# ERC_Sch_1.net
KiCad netlist of a schematic drawn in EAGLE
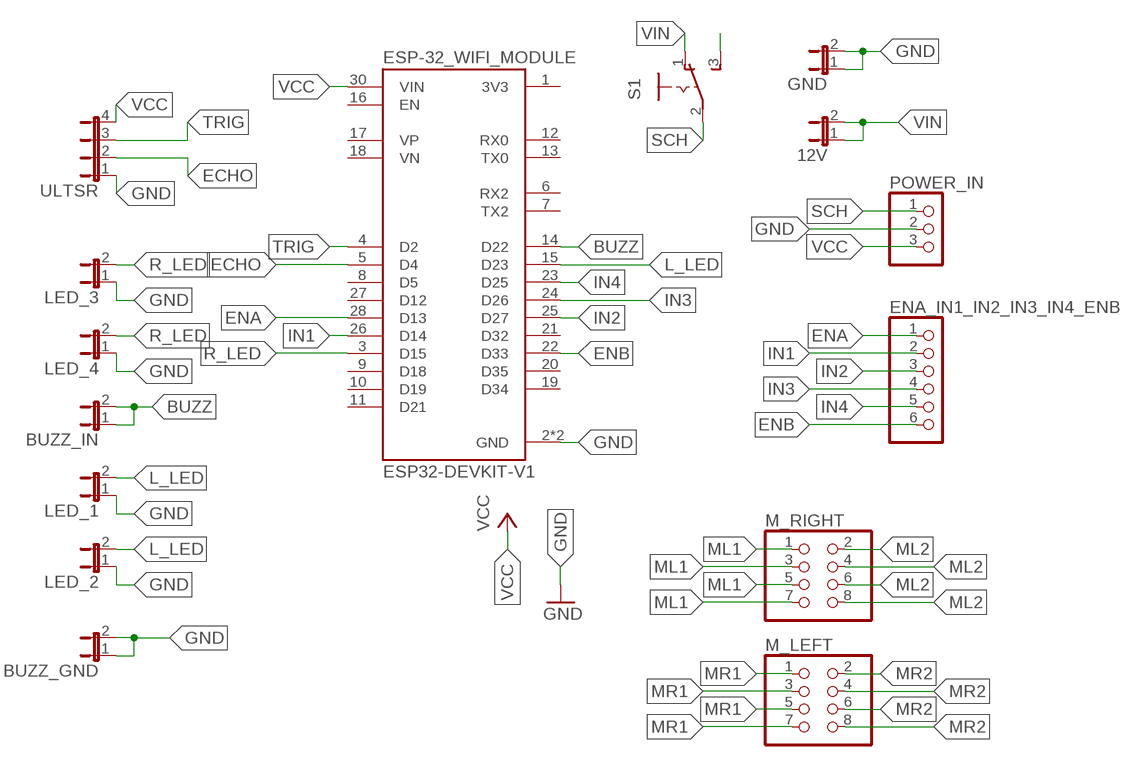
[diagram p0: schematic, sheet 1]

(export (version "E")
  (design (tool "Eeschema 10.0.6"))
  (components
    (comp (ref "12V")
      (value "JP1E")
      (footprint "eagle-import:JP1")
      (libsource (lib "eagle-import") (part "JP1E"))
    )
    (comp (ref "BUZZ_GND")
      (value "JP1E")
      (footprint "eagle-import:JP1")
      (libsource (lib "eagle-import") (part "JP1E"))
    )
    (comp (ref "BUZZ_IN")
      (value "JP1E")
      (footprint "eagle-import:JP1")
      (libsource (lib "eagle-import") (part "JP1E"))
    )
    (comp (ref "ENA_IN1_IN2_IN3_IN4_ENB")
      (value "PINHD-1X6")
      (footprint "eagle-import:1X06")
      (libsource (lib "eagle-import") (part "PINHD-1X6"))
    )
    (comp (ref "ESP-32_WIFI_MODULE")
      (value "ESP32-DEVKIT-V1")
      (footprint "eagle-import:MODULE_ESP32_DEVKIT_V1")
      (fields (field (name "MF") "Do it"))
      (libsource (lib "eagle-import") (part "ESP32-DEVKIT-V1"))
    )
    (comp (ref "GND")
      (value "JP1E")
      (footprint "eagle-import:JP1")
      (libsource (lib "eagle-import") (part "JP1E"))
    )
    (comp (ref "LED_1")
      (value "JP1E")
      (footprint "eagle-import:JP1")
      (libsource (lib "eagle-import") (part "JP1E"))
    )
    (comp (ref "LED_2")
      (value "JP1E")
      (footprint "eagle-import:JP1")
      (libsource (lib "eagle-import") (part "JP1E"))
    )
    (comp (ref "LED_3")
      (value "JP1E")
      (footprint "eagle-import:JP1")
      (libsource (lib "eagle-import") (part "JP1E"))
    )
    (comp (ref "LED_4")
      (value "JP1E")
      (footprint "eagle-import:JP1")
      (libsource (lib "eagle-import") (part "JP1E"))
    )
    (comp (ref "M_LEFT")
      (value "PINHD-2X4")
      (footprint "eagle-import:2X04")
      (libsource (lib "eagle-import") (part "PINHD-2X4"))
    )
    (comp (ref "M_RIGHT")
      (value "PINHD-2X4")
      (footprint "eagle-import:2X04")
      (libsource (lib "eagle-import") (part "PINHD-2X4"))
    )
    (comp (ref "POWER_IN")
      (value "PINHD-1X3")
      (footprint "eagle-import:1X03")
      (libsource (lib "eagle-import") (part "PINHD-1X3"))
    )
    (comp (ref "S1")
      (value "255SB")
      (footprint "eagle-import:255SB")
      (libsource (lib "eagle-import") (part "255SB"))
    )
    (comp (ref "ULTSR")
      (value "JP4E")
      (footprint "eagle-import:JP4")
      (libsource (lib "eagle-import") (part "JP4E"))
    )
  )
  (nets
    (net (code "1") (name "BUZZ") (class "Default")
      (node (ref "BUZZ_IN") (pin "1") (pinfunction "1_1") (pintype "passive"))
      (node (ref "BUZZ_IN") (pin "2") (pinfunction "2_2") (pintype "passive"))
      (node (ref "ESP-32_WIFI_MODULE") (pin "14") (pinfunction "D22_14") (pintype "bidirectional"))
    )
    (net (code "2") (name "ECHO") (class "Default")
      (node (ref "ESP-32_WIFI_MODULE") (pin "5") (pinfunction "D4_5") (pintype "bidirectional"))
      (node (ref "ULTSR") (pin "2") (pinfunction "2_2") (pintype "passive"))
    )
    (net (code "3") (name "ENA") (class "Default")
      (node (ref "ENA_IN1_IN2_IN3_IN4_ENB") (pin "1") (pinfunction "1_1") (pintype "passive"))
      (node (ref "ESP-32_WIFI_MODULE") (pin "28") (pinfunction "D13_28") (pintype "bidirectional"))
    )
    (net (code "4") (name "ENB") (class "Default")
      (node (ref "ENA_IN1_IN2_IN3_IN4_ENB") (pin "6") (pinfunction "6_6") (pintype "passive"))
      (node (ref "ESP-32_WIFI_MODULE") (pin "22") (pinfunction "D33_22") (pintype "bidirectional"))
    )
    (net (code "5") (name "GND") (class "Default")
      (node (ref "BUZZ_GND") (pin "1") (pinfunction "1_1") (pintype "passive"))
      (node (ref "BUZZ_GND") (pin "2") (pinfunction "2_2") (pintype "passive"))
      (node (ref "ESP-32_WIFI_MODULE") (pin "2") (pinfunction "GND_2") (pintype "power_in"))
      (node (ref "ESP-32_WIFI_MODULE") (pin "29") (pinfunction "GND_29") (pintype "power_in"))
      (node (ref "GND") (pin "1") (pinfunction "1_1") (pintype "passive"))
      (node (ref "GND") (pin "2") (pinfunction "2_2") (pintype "passive"))
      (node (ref "LED_1") (pin "1") (pinfunction "1_1") (pintype "passive"))
      (node (ref "LED_2") (pin "1") (pinfunction "1_1") (pintype "passive"))
      (node (ref "LED_3") (pin "1") (pinfunction "1_1") (pintype "passive"))
      (node (ref "LED_4") (pin "1") (pinfunction "1_1") (pintype "passive"))
      (node (ref "POWER_IN") (pin "2") (pinfunction "2_2") (pintype "passive"))
      (node (ref "ULTSR") (pin "1") (pinfunction "1_1") (pintype "passive"))
    )
    (net (code "6") (name "IN1") (class "Default")
      (node (ref "ENA_IN1_IN2_IN3_IN4_ENB") (pin "2") (pinfunction "2_2") (pintype "passive"))
      (node (ref "ESP-32_WIFI_MODULE") (pin "26") (pinfunction "D14_26") (pintype "bidirectional"))
    )
    (net (code "7") (name "IN2") (class "Default")
      (node (ref "ENA_IN1_IN2_IN3_IN4_ENB") (pin "3") (pinfunction "3_3") (pintype "passive"))
      (node (ref "ESP-32_WIFI_MODULE") (pin "25") (pinfunction "D27_25") (pintype "bidirectional"))
    )
    (net (code "8") (name "IN3") (class "Default")
      (node (ref "ENA_IN1_IN2_IN3_IN4_ENB") (pin "4") (pinfunction "4_4") (pintype "passive"))
      (node (ref "ESP-32_WIFI_MODULE") (pin "24") (pinfunction "D26_24") (pintype "bidirectional"))
    )
    (net (code "9") (name "IN4") (class "Default")
      (node (ref "ENA_IN1_IN2_IN3_IN4_ENB") (pin "5") (pinfunction "5_5") (pintype "passive"))
      (node (ref "ESP-32_WIFI_MODULE") (pin "23") (pinfunction "D25_23") (pintype "bidirectional"))
    )
    (net (code "10") (name "L_LED") (class "Default")
      (node (ref "ESP-32_WIFI_MODULE") (pin "15") (pinfunction "D23_15") (pintype "bidirectional"))
      (node (ref "LED_1") (pin "2") (pinfunction "2_2") (pintype "passive"))
      (node (ref "LED_2") (pin "2") (pinfunction "2_2") (pintype "passive"))
    )
    (net (code "11") (name "ML1") (class "Default")
      (node (ref "M_RIGHT") (pin "1") (pinfunction "1_1") (pintype "passive"))
      (node (ref "M_RIGHT") (pin "3") (pinfunction "3_3") (pintype "passive"))
      (node (ref "M_RIGHT") (pin "5") (pinfunction "5_5") (pintype "passive"))
      (node (ref "M_RIGHT") (pin "7") (pinfunction "7_7") (pintype "passive"))
    )
    (net (code "12") (name "ML2") (class "Default")
      (node (ref "M_RIGHT") (pin "2") (pinfunction "2_2") (pintype "passive"))
      (node (ref "M_RIGHT") (pin "4") (pinfunction "4_4") (pintype "passive"))
      (node (ref "M_RIGHT") (pin "6") (pinfunction "6_6") (pintype "passive"))
      (node (ref "M_RIGHT") (pin "8") (pinfunction "8_8") (pintype "passive"))
    )
    (net (code "13") (name "MR1") (class "Default")
      (node (ref "M_LEFT") (pin "1") (pinfunction "1_1") (pintype "passive"))
      (node (ref "M_LEFT") (pin "3") (pinfunction "3_3") (pintype "passive"))
      (node (ref "M_LEFT") (pin "5") (pinfunction "5_5") (pintype "passive"))
      (node (ref "M_LEFT") (pin "7") (pinfunction "7_7") (pintype "passive"))
    )
    (net (code "14") (name "MR2") (class "Default")
      (node (ref "M_LEFT") (pin "2") (pinfunction "2_2") (pintype "passive"))
      (node (ref "M_LEFT") (pin "4") (pinfunction "4_4") (pintype "passive"))
      (node (ref "M_LEFT") (pin "6") (pinfunction "6_6") (pintype "passive"))
      (node (ref "M_LEFT") (pin "8") (pinfunction "8_8") (pintype "passive"))
    )
    (net (code "15") (name "R_LED") (class "Default")
      (node (ref "ESP-32_WIFI_MODULE") (pin "3") (pinfunction "D15_3") (pintype "bidirectional"))
      (node (ref "LED_3") (pin "2") (pinfunction "2_2") (pintype "passive"))
      (node (ref "LED_4") (pin "2") (pinfunction "2_2") (pintype "passive"))
    )
    (net (code "16") (name "SCH") (class "Default")
      (node (ref "POWER_IN") (pin "1") (pinfunction "1_1") (pintype "passive"))
      (node (ref "S1") (pin "2") (pinfunction "P_2") (pintype "passive"))
    )
    (net (code "17") (name "TRIG") (class "Default")
      (node (ref "ESP-32_WIFI_MODULE") (pin "4") (pinfunction "D2_4") (pintype "bidirectional"))
      (node (ref "ULTSR") (pin "3") (pinfunction "3_3") (pintype "passive"))
    )
    (net (code "18") (name "VCC") (class "Default")
      (node (ref "ESP-32_WIFI_MODULE") (pin "30") (pinfunction "VIN_30") (pintype "input"))
      (node (ref "POWER_IN") (pin "3") (pinfunction "3_3") (pintype "passive"))
      (node (ref "ULTSR") (pin "4") (pinfunction "4_4") (pintype "passive"))
    )
    (net (code "19") (name "VIN") (class "Default")
      (node (ref "12V") (pin "1") (pinfunction "1_1") (pintype "passive"))
      (node (ref "12V") (pin "2") (pinfunction "2_2") (pintype "passive"))
      (node (ref "S1") (pin "1") (pinfunction "O_1") (pintype "passive"))
    )
    (net (code "20") (name "unconnected-(ESP-32_WIFI_MODULE-3V3-Pad1)") (class "Default")
      (node (ref "ESP-32_WIFI_MODULE") (pin "1") (pinfunction "3V3_1") (pintype "output"))
    )
    (net (code "21") (name "unconnected-(ESP-32_WIFI_MODULE-D5-Pad8)") (class "Default")
      (node (ref "ESP-32_WIFI_MODULE") (pin "8") (pinfunction "D5_8") (pintype "bidirectional"))
    )
    (net (code "22") (name "unconnected-(ESP-32_WIFI_MODULE-D12-Pad27)") (class "Default")
      (node (ref "ESP-32_WIFI_MODULE") (pin "27") (pinfunction "D12_27") (pintype "bidirectional"))
    )
    (net (code "23") (name "unconnected-(ESP-32_WIFI_MODULE-D18-Pad9)") (class "Default")
      (node (ref "ESP-32_WIFI_MODULE") (pin "9") (pinfunction "D18_9") (pintype "bidirectional"))
    )
    (net (code "24") (name "unconnected-(ESP-32_WIFI_MODULE-D19-Pad10)") (class "Default")
      (node (ref "ESP-32_WIFI_MODULE") (pin "10") (pinfunction "D19_10") (pintype "bidirectional"))
    )
    (net (code "25") (name "unconnected-(ESP-32_WIFI_MODULE-D21-Pad11)") (class "Default")
      (node (ref "ESP-32_WIFI_MODULE") (pin "11") (pinfunction "D21_11") (pintype "bidirectional"))
    )
    (net (code "26") (name "unconnected-(ESP-32_WIFI_MODULE-D32-Pad21)") (class "Default")
      (node (ref "ESP-32_WIFI_MODULE") (pin "21") (pinfunction "D32_21") (pintype "bidirectional"))
    )
    (net (code "27") (name "unconnected-(ESP-32_WIFI_MODULE-D34-Pad19)") (class "Default")
      (node (ref "ESP-32_WIFI_MODULE") (pin "19") (pinfunction "D34_19") (pintype "bidirectional"))
    )
    (net (code "28") (name "unconnected-(ESP-32_WIFI_MODULE-D35-Pad20)") (class "Default")
      (node (ref "ESP-32_WIFI_MODULE") (pin "20") (pinfunction "D35_20") (pintype "bidirectional"))
    )
    (net (code "29") (name "unconnected-(ESP-32_WIFI_MODULE-EN-Pad16)") (class "Default")
      (node (ref "ESP-32_WIFI_MODULE") (pin "16") (pinfunction "EN_16") (pintype "input"))
    )
    (net (code "30") (name "unconnected-(ESP-32_WIFI_MODULE-RX0-Pad12)") (class "Default")
      (node (ref "ESP-32_WIFI_MODULE") (pin "12") (pinfunction "RX0_12") (pintype "input"))
    )
    (net (code "31") (name "unconnected-(ESP-32_WIFI_MODULE-RX2-Pad6)") (class "Default")
      (node (ref "ESP-32_WIFI_MODULE") (pin "6") (pinfunction "RX2_6") (pintype "input"))
    )
    (net (code "32") (name "unconnected-(ESP-32_WIFI_MODULE-TX0-Pad13)") (class "Default")
      (node (ref "ESP-32_WIFI_MODULE") (pin "13") (pinfunction "TX0_13") (pintype "output"))
    )
    (net (code "33") (name "unconnected-(ESP-32_WIFI_MODULE-TX2-Pad7)") (class "Default")
      (node (ref "ESP-32_WIFI_MODULE") (pin "7") (pinfunction "TX2_7") (pintype "output"))
    )
    (net (code "34") (name "unconnected-(ESP-32_WIFI_MODULE-VN-Pad18)") (class "Default")
      (node (ref "ESP-32_WIFI_MODULE") (pin "18") (pinfunction "VN_18") (pintype "bidirectional"))
    )
    (net (code "35") (name "unconnected-(ESP-32_WIFI_MODULE-VP-Pad17)") (class "Default")
      (node (ref "ESP-32_WIFI_MODULE") (pin "17") (pinfunction "VP_17") (pintype "bidirectional"))
    )
    (net (code "36") (name "unconnected-(S1-S-Pad3)") (class "Default")
      (node (ref "S1") (pin "3") (pinfunction "S_3") (pintype "passive"))
    )
  )
)
